# LEDmeterboard4mmRised.net
KiCad netlist of a schematic drawn in EAGLE
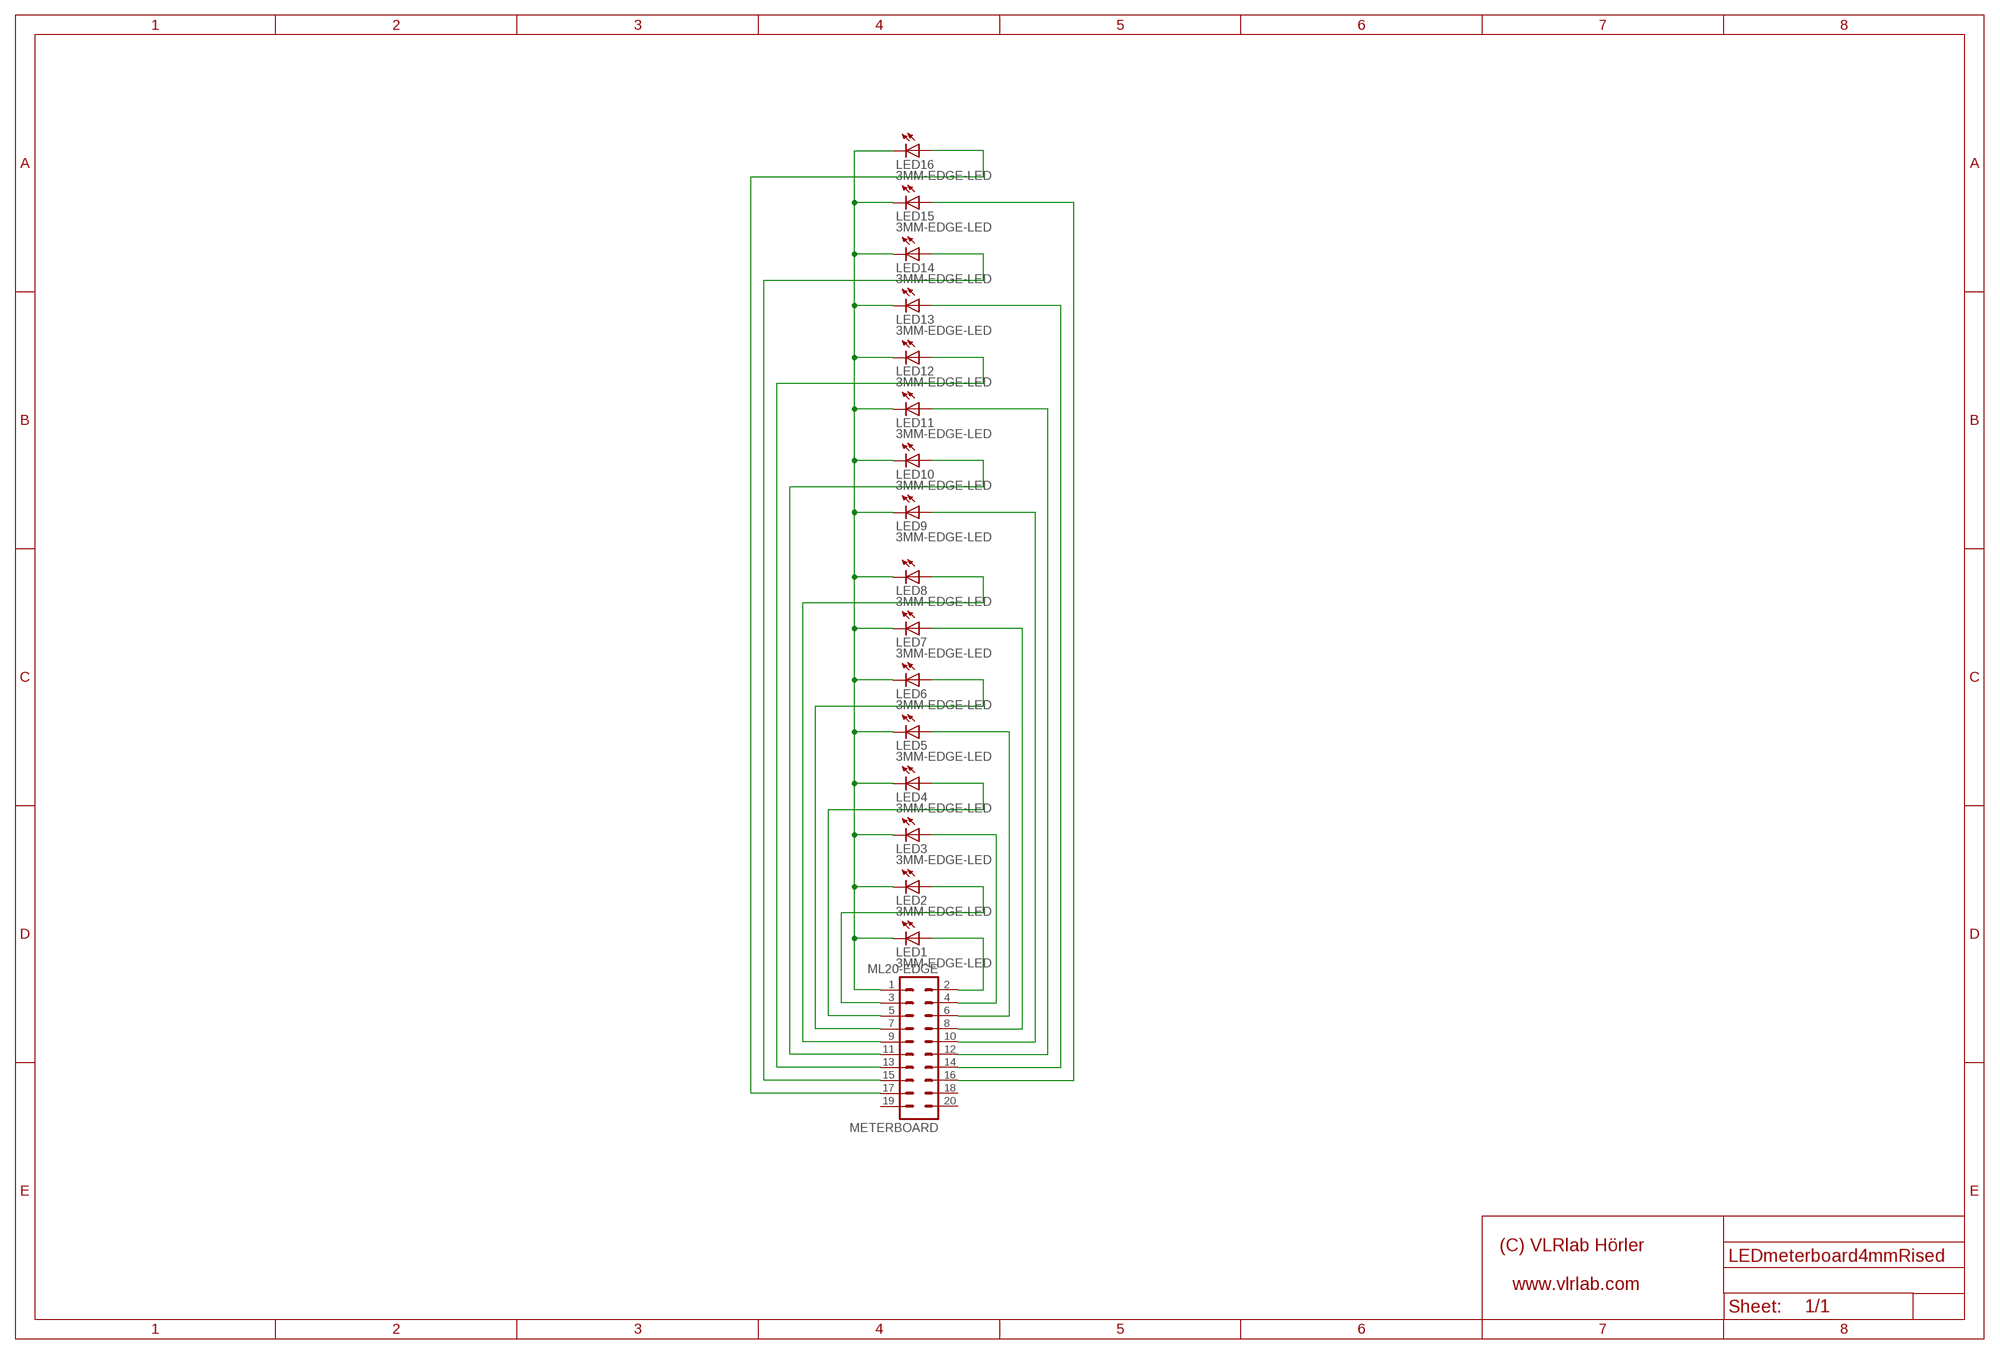
[diagram p0: schematic, sheet 1]

(export (version "E")
  (design (tool "Eeschema 10.0.6"))
  (components
    (comp (ref "LED1")
      (value "3MM-EDGE-LED")
      (footprint "eagle-import:3MM-EDGE-LED")
      (libsource (lib "eagle-import") (part "3MM-EDGE-LED"))
    )
    (comp (ref "LED2")
      (value "3MM-EDGE-LED")
      (footprint "eagle-import:3MM-EDGE-LED")
      (libsource (lib "eagle-import") (part "3MM-EDGE-LED"))
    )
    (comp (ref "LED3")
      (value "3MM-EDGE-LED")
      (footprint "eagle-import:3MM-EDGE-LED")
      (libsource (lib "eagle-import") (part "3MM-EDGE-LED"))
    )
    (comp (ref "LED4")
      (value "3MM-EDGE-LED")
      (footprint "eagle-import:3MM-EDGE-LED")
      (libsource (lib "eagle-import") (part "3MM-EDGE-LED"))
    )
    (comp (ref "LED5")
      (value "3MM-EDGE-LED")
      (footprint "eagle-import:3MM-EDGE-LED")
      (libsource (lib "eagle-import") (part "3MM-EDGE-LED"))
    )
    (comp (ref "LED6")
      (value "3MM-EDGE-LED")
      (footprint "eagle-import:3MM-EDGE-LED")
      (libsource (lib "eagle-import") (part "3MM-EDGE-LED"))
    )
    (comp (ref "LED7")
      (value "3MM-EDGE-LED")
      (footprint "eagle-import:3MM-EDGE-LED")
      (libsource (lib "eagle-import") (part "3MM-EDGE-LED"))
    )
    (comp (ref "LED8")
      (value "3MM-EDGE-LED")
      (footprint "eagle-import:3MM-EDGE-LED")
      (libsource (lib "eagle-import") (part "3MM-EDGE-LED"))
    )
    (comp (ref "LED9")
      (value "3MM-EDGE-LED")
      (footprint "eagle-import:3MM-EDGE-LED")
      (libsource (lib "eagle-import") (part "3MM-EDGE-LED"))
    )
    (comp (ref "LED10")
      (value "3MM-EDGE-LED")
      (footprint "eagle-import:3MM-EDGE-LED")
      (libsource (lib "eagle-import") (part "3MM-EDGE-LED"))
    )
    (comp (ref "LED11")
      (value "3MM-EDGE-LED")
      (footprint "eagle-import:3MM-EDGE-LED")
      (libsource (lib "eagle-import") (part "3MM-EDGE-LED"))
    )
    (comp (ref "LED12")
      (value "3MM-EDGE-LED")
      (footprint "eagle-import:3MM-EDGE-LED")
      (libsource (lib "eagle-import") (part "3MM-EDGE-LED"))
    )
    (comp (ref "LED13")
      (value "3MM-EDGE-LED")
      (footprint "eagle-import:3MM-EDGE-LED")
      (libsource (lib "eagle-import") (part "3MM-EDGE-LED"))
    )
    (comp (ref "LED14")
      (value "3MM-EDGE-LED")
      (footprint "eagle-import:3MM-EDGE-LED")
      (libsource (lib "eagle-import") (part "3MM-EDGE-LED"))
    )
    (comp (ref "LED15")
      (value "3MM-EDGE-LED")
      (footprint "eagle-import:3MM-EDGE-LED")
      (libsource (lib "eagle-import") (part "3MM-EDGE-LED"))
    )
    (comp (ref "LED16")
      (value "3MM-EDGE-LED")
      (footprint "eagle-import:3MM-EDGE-LED")
      (libsource (lib "eagle-import") (part "3MM-EDGE-LED"))
    )
    (comp (ref "METERBOARD")
      (value "ML20-EDGE")
      (footprint "eagle-import:ML20EDGE")
      (libsource (lib "eagle-import") (part "ML20-EDGE"))
    )
  )
  (nets
    (net (code "1") (name "Net-(LED1-A)") (class "Default")
      (node (ref "LED1") (pin "ANODE") (pinfunction "A_ANODE") (pintype "passive"))
      (node (ref "METERBOARD") (pin "2") (pinfunction "2_2") (pintype "passive"))
    )
    (net (code "2") (name "Net-(LED1-C)") (class "Default")
      (node (ref "LED1") (pin "KATHODE") (pinfunction "C_KATHODE") (pintype "passive"))
      (node (ref "LED10") (pin "KATHODE") (pinfunction "C_KATHODE") (pintype "passive"))
      (node (ref "LED11") (pin "KATHODE") (pinfunction "C_KATHODE") (pintype "passive"))
      (node (ref "LED12") (pin "KATHODE") (pinfunction "C_KATHODE") (pintype "passive"))
      (node (ref "LED13") (pin "KATHODE") (pinfunction "C_KATHODE") (pintype "passive"))
      (node (ref "LED14") (pin "KATHODE") (pinfunction "C_KATHODE") (pintype "passive"))
      (node (ref "LED15") (pin "KATHODE") (pinfunction "C_KATHODE") (pintype "passive"))
      (node (ref "LED16") (pin "KATHODE") (pinfunction "C_KATHODE") (pintype "passive"))
      (node (ref "LED2") (pin "KATHODE") (pinfunction "C_KATHODE") (pintype "passive"))
      (node (ref "LED3") (pin "KATHODE") (pinfunction "C_KATHODE") (pintype "passive"))
      (node (ref "LED4") (pin "KATHODE") (pinfunction "C_KATHODE") (pintype "passive"))
      (node (ref "LED5") (pin "KATHODE") (pinfunction "C_KATHODE") (pintype "passive"))
      (node (ref "LED6") (pin "KATHODE") (pinfunction "C_KATHODE") (pintype "passive"))
      (node (ref "LED7") (pin "KATHODE") (pinfunction "C_KATHODE") (pintype "passive"))
      (node (ref "LED8") (pin "KATHODE") (pinfunction "C_KATHODE") (pintype "passive"))
      (node (ref "LED9") (pin "KATHODE") (pinfunction "C_KATHODE") (pintype "passive"))
      (node (ref "METERBOARD") (pin "1") (pinfunction "1_1") (pintype "passive"))
    )
    (net (code "3") (name "Net-(LED2-A)") (class "Default")
      (node (ref "LED2") (pin "ANODE") (pinfunction "A_ANODE") (pintype "passive"))
      (node (ref "METERBOARD") (pin "3") (pinfunction "3_3") (pintype "passive"))
    )
    (net (code "4") (name "Net-(LED3-A)") (class "Default")
      (node (ref "LED3") (pin "ANODE") (pinfunction "A_ANODE") (pintype "passive"))
      (node (ref "METERBOARD") (pin "4") (pinfunction "4_4") (pintype "passive"))
    )
    (net (code "5") (name "Net-(LED4-A)") (class "Default")
      (node (ref "LED4") (pin "ANODE") (pinfunction "A_ANODE") (pintype "passive"))
      (node (ref "METERBOARD") (pin "5") (pinfunction "5_5") (pintype "passive"))
    )
    (net (code "6") (name "Net-(LED5-A)") (class "Default")
      (node (ref "LED5") (pin "ANODE") (pinfunction "A_ANODE") (pintype "passive"))
      (node (ref "METERBOARD") (pin "6") (pinfunction "6_6") (pintype "passive"))
    )
    (net (code "7") (name "Net-(LED6-A)") (class "Default")
      (node (ref "LED6") (pin "ANODE") (pinfunction "A_ANODE") (pintype "passive"))
      (node (ref "METERBOARD") (pin "7") (pinfunction "7_7") (pintype "passive"))
    )
    (net (code "8") (name "Net-(LED7-A)") (class "Default")
      (node (ref "LED7") (pin "ANODE") (pinfunction "A_ANODE") (pintype "passive"))
      (node (ref "METERBOARD") (pin "8") (pinfunction "8_8") (pintype "passive"))
    )
    (net (code "9") (name "Net-(LED8-A)") (class "Default")
      (node (ref "LED8") (pin "ANODE") (pinfunction "A_ANODE") (pintype "passive"))
      (node (ref "METERBOARD") (pin "9") (pinfunction "9_9") (pintype "passive"))
    )
    (net (code "10") (name "Net-(LED9-A)") (class "Default")
      (node (ref "LED9") (pin "ANODE") (pinfunction "A_ANODE") (pintype "passive"))
      (node (ref "METERBOARD") (pin "10") (pinfunction "10_10") (pintype "passive"))
    )
    (net (code "11") (name "Net-(LED10-A)") (class "Default")
      (node (ref "LED10") (pin "ANODE") (pinfunction "A_ANODE") (pintype "passive"))
      (node (ref "METERBOARD") (pin "11") (pinfunction "11_11") (pintype "passive"))
    )
    (net (code "12") (name "Net-(LED11-A)") (class "Default")
      (node (ref "LED11") (pin "ANODE") (pinfunction "A_ANODE") (pintype "passive"))
      (node (ref "METERBOARD") (pin "12") (pinfunction "12_12") (pintype "passive"))
    )
    (net (code "13") (name "Net-(LED12-A)") (class "Default")
      (node (ref "LED12") (pin "ANODE") (pinfunction "A_ANODE") (pintype "passive"))
      (node (ref "METERBOARD") (pin "13") (pinfunction "13_13") (pintype "passive"))
    )
    (net (code "14") (name "Net-(LED13-A)") (class "Default")
      (node (ref "LED13") (pin "ANODE") (pinfunction "A_ANODE") (pintype "passive"))
      (node (ref "METERBOARD") (pin "14") (pinfunction "14_14") (pintype "passive"))
    )
    (net (code "15") (name "Net-(LED14-A)") (class "Default")
      (node (ref "LED14") (pin "ANODE") (pinfunction "A_ANODE") (pintype "passive"))
      (node (ref "METERBOARD") (pin "15") (pinfunction "15_15") (pintype "passive"))
    )
    (net (code "16") (name "Net-(LED15-A)") (class "Default")
      (node (ref "LED15") (pin "ANODE") (pinfunction "A_ANODE") (pintype "passive"))
      (node (ref "METERBOARD") (pin "16") (pinfunction "16_16") (pintype "passive"))
    )
    (net (code "17") (name "Net-(LED16-A)") (class "Default")
      (node (ref "LED16") (pin "ANODE") (pinfunction "A_ANODE") (pintype "passive"))
      (node (ref "METERBOARD") (pin "17") (pinfunction "17_17") (pintype "passive"))
    )
    (net (code "18") (name "unconnected-(METERBOARD-Pad18)") (class "Default")
      (node (ref "METERBOARD") (pin "18") (pinfunction "18_18") (pintype "passive"))
    )
    (net (code "19") (name "unconnected-(METERBOARD-Pad19)") (class "Default")
      (node (ref "METERBOARD") (pin "19") (pinfunction "19_19") (pintype "passive"))
    )
    (net (code "20") (name "unconnected-(METERBOARD-Pad20)") (class "Default")
      (node (ref "METERBOARD") (pin "20") (pinfunction "20_20") (pintype "passive"))
    )
  )
)
